# Board_V07B.net
KiCad netlist of a schematic drawn in EAGLE
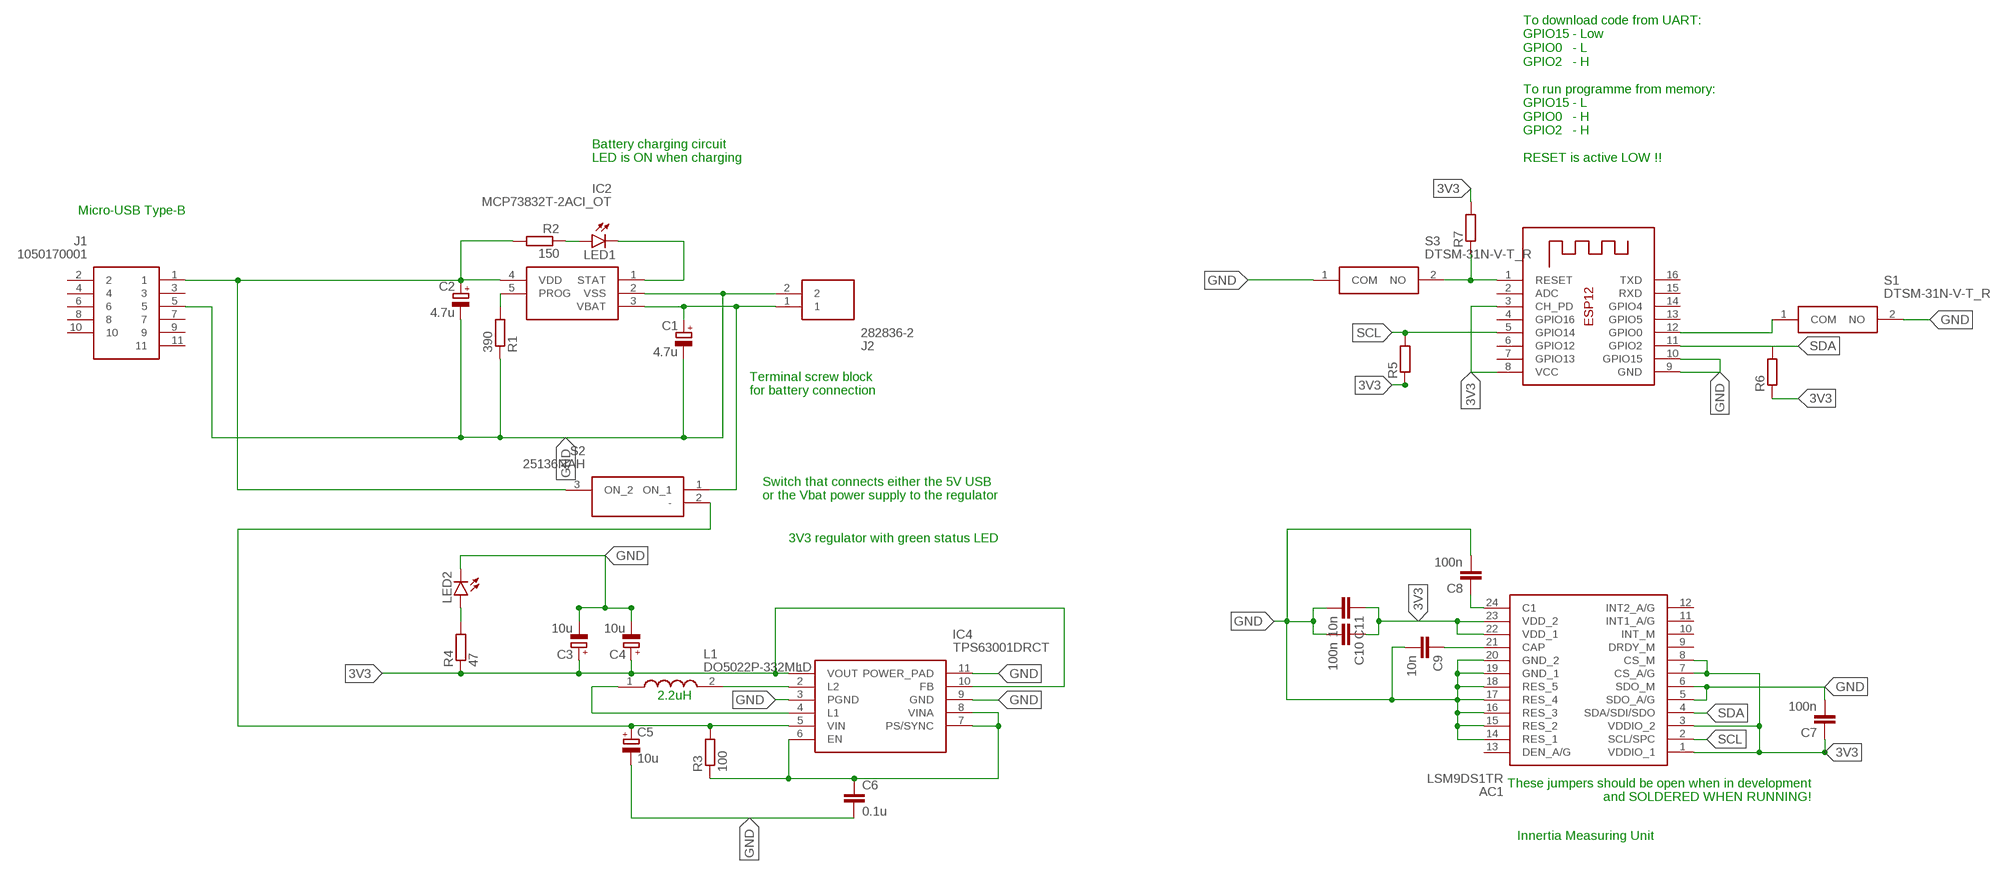
[diagram p0: schematic, sheet 1]

(export (version "E")
  (design (tool "Eeschema 10.0.6"))
  (components
    (comp (ref "AC1")
      (value "LSM9DS1TR")
      (footprint "eagle-import:LGA-24L(3X3.5X1MM)")
      (fields (field (name "MOUSER_PART_NUMBER") "511-LSM9DS1TR") (field (name "RS_PART_NUMBER") "1660908"))
      (libsource (lib "eagle-import") (part "LSM9DS1TR"))
    )
    (comp (ref "C1")
      (value "4.7u")
      (footprint "eagle-import:D_7343-31R")
      (libsource (lib "eagle-import") (part "CPOL-EUD/7343-31R"))
    )
    (comp (ref "C2")
      (value "4.7u")
      (footprint "eagle-import:D_7343-31R")
      (libsource (lib "eagle-import") (part "CPOL-EUD/7343-31R"))
    )
    (comp (ref "C3")
      (value "10u")
      (footprint "eagle-import:D_7343-31R")
      (libsource (lib "eagle-import") (part "CPOL-EUD/7343-31R"))
    )
    (comp (ref "C4")
      (value "10u")
      (footprint "eagle-import:D_7343-31R")
      (libsource (lib "eagle-import") (part "CPOL-EUD/7343-31R"))
    )
    (comp (ref "C5")
      (value "10u")
      (footprint "eagle-import:D_7343-31R")
      (libsource (lib "eagle-import") (part "CPOL-EUD/7343-31R"))
    )
    (comp (ref "C6")
      (value "0.1u")
      (footprint "eagle-import:C0402")
      (libsource (lib "eagle-import") (part "C-EUC0402"))
    )
    (comp (ref "C7")
      (value "100n")
      (footprint "eagle-import:C0805")
      (libsource (lib "eagle-import") (part "C-EUC0805"))
    )
    (comp (ref "C8")
      (value "100n")
      (footprint "eagle-import:C0805")
      (libsource (lib "eagle-import") (part "C-EUC0805"))
    )
    (comp (ref "C9")
      (value "10n")
      (footprint "eagle-import:C0805")
      (libsource (lib "eagle-import") (part "C-EUC0805"))
    )
    (comp (ref "C10")
      (value "100n")
      (footprint "eagle-import:C0805")
      (libsource (lib "eagle-import") (part "C-EUC0805"))
    )
    (comp (ref "C11")
      (value "10n")
      (footprint "eagle-import:C0805")
      (libsource (lib "eagle-import") (part "C-EUC0805"))
    )
    (comp (ref "IC2")
      (value "MCP73832T-2ACI_OT")
      (footprint "eagle-import:SOT95P270X145-5N")
      (fields
        (field (name "MANUFACTURER_PART_NUMBER") "MCP73832T-2ACI/OT")
        (field (name "MOUSER_PART_NUMBER") "579-MCP73832T-2ACIOT")
        (field (name "RS_PART_NUMBER") "9122897")
      )
      (libsource (lib "eagle-import") (part "MCP73832T-2ACI_OT"))
    )
    (comp (ref "IC4")
      (value "TPS63001DRCT")
      (footprint "eagle-import:SON50P300X300X100-11N")
      (fields (field (name "RS_PART_NUMBER") "7968405"))
      (libsource (lib "eagle-import") (part "TPS63001DRCT"))
    )
    (comp (ref "J1")
      (value "1050170001")
      (footprint "eagle-import:MICROUSB-BTYPE")
      (libsource (lib "eagle-import") (part "1050170001"))
    )
    (comp (ref "J2")
      (value "282836-2")
      (footprint "eagle-import:SHDR2W100P0X500_1X2_1000X820X1")
      (fields (field (name "MOUSER_PART_NUMBER") "571-2828362") (field (name "RS_PART_NUMBER") "1354983"))
      (libsource (lib "eagle-import") (part "282836-2"))
    )
    (comp (ref "L1")
      (value "DO5022P-332MLD")
      (footprint "eagle-import:DO5022P-104MLD")
      (fields (field (name "MOUSER_PART_NUMBER") "994-DO5022P-332MLD"))
      (libsource (lib "eagle-import") (part "DO5022P-332MLD"))
    )
    (comp (ref "LED1")
      (value "LED5MM")
      (footprint "eagle-import:LED5MM")
      (libsource (lib "eagle-import") (part "LED5MM"))
    )
    (comp (ref "LED2")
      (value "LED5MM")
      (footprint "eagle-import:LED5MM")
      (libsource (lib "eagle-import") (part "LED5MM"))
    )
    (comp (ref "R1")
      (value "390")
      (footprint "eagle-import:R0805")
      (libsource (lib "eagle-import") (part "R-EU_R0805"))
    )
    (comp (ref "R2")
      (value "150")
      (footprint "eagle-import:R0805")
      (libsource (lib "eagle-import") (part "R-EU_R0805"))
    )
    (comp (ref "R3")
      (value "100")
      (footprint "eagle-import:R0805")
      (libsource (lib "eagle-import") (part "R-EU_R0805"))
    )
    (comp (ref "R4")
      (value "47")
      (footprint "eagle-import:R0805")
      (libsource (lib "eagle-import") (part "R-EU_R0805"))
    )
    (comp (ref "R5")
      (value "R-EU_R0805")
      (footprint "eagle-import:R0805")
      (libsource (lib "eagle-import") (part "R-EU_R0805"))
    )
    (comp (ref "R6")
      (value "R-EU_R0805")
      (footprint "eagle-import:R0805")
      (libsource (lib "eagle-import") (part "R-EU_R0805"))
    )
    (comp (ref "R7")
      (value "R-EU_R0805")
      (footprint "eagle-import:R0805")
      (libsource (lib "eagle-import") (part "R-EU_R0805"))
    )
    (comp (ref "S1")
      (value "DTSM-31N-V-T_R")
      (footprint "eagle-import:DTSM32NVTR")
      (fields
        (field (name "MANUFACTURER_PART_NUMBER") "DTSM-31N-V-T/R")
        (field (name "MOUSER_PART_NUMBER") "113-DTSM31NVTR")
      )
      (libsource (lib "eagle-import") (part "DTSM-31N-V-T_R"))
    )
    (comp (ref "S2")
      (value "25136NAH")
      (footprint "eagle-import:25136NAH")
      (fields (field (name "MOUSER_PART_NUMBER") "642-25136NAH") (field (name "RS_PART_NUMBER") "0339673A"))
      (libsource (lib "eagle-import") (part "25136NAH"))
    )
    (comp (ref "S3")
      (value "DTSM-31N-V-T_R")
      (footprint "eagle-import:DTSM32NVTR")
      (fields
        (field (name "MANUFACTURER_PART_NUMBER") "DTSM-31N-V-T/R")
        (field (name "MOUSER_PART_NUMBER") "113-DTSM31NVTR")
      )
      (libsource (lib "eagle-import") (part "DTSM-31N-V-T_R"))
    )
    (comp (ref "X1")
      (value "ESP-12")
      (footprint "eagle-import:ESP-12")
      (libsource (lib "eagle-import") (part "ESP-12"))
    )
  )
  (nets
    (net (code "1") (name "3V3") (class "Default")
      (node (ref "AC1") (pin "1") (pinfunction "VDDIO_1_1") (pintype "power_in"))
      (node (ref "AC1") (pin "22") (pinfunction "VDD_1_22") (pintype "power_in"))
      (node (ref "AC1") (pin "23") (pinfunction "VDD_2_23") (pintype "power_in"))
      (node (ref "AC1") (pin "3") (pinfunction "VDDIO_2_3") (pintype "power_in"))
      (node (ref "AC1") (pin "7") (pinfunction "CS_A/G_7") (pintype "bidirectional"))
      (node (ref "AC1") (pin "8") (pinfunction "CS_M_8") (pintype "bidirectional"))
      (node (ref "C10") (pin "1") (pinfunction "1_1") (pintype "passive"))
      (node (ref "C11") (pin "1") (pinfunction "1_1") (pintype "passive"))
      (node (ref "C3") (pin "+") (pinfunction "+_+") (pintype "passive"))
      (node (ref "C4") (pin "+") (pinfunction "+_+") (pintype "passive"))
      (node (ref "C7") (pin "1") (pinfunction "1_1") (pintype "passive"))
      (node (ref "IC4") (pin "1") (pinfunction "VOUT_1") (pintype "bidirectional"))
      (node (ref "IC4") (pin "10") (pinfunction "FB_10") (pintype "bidirectional"))
      (node (ref "R4") (pin "1") (pinfunction "1_1") (pintype "passive"))
      (node (ref "R5") (pin "1") (pinfunction "1_1") (pintype "passive"))
      (node (ref "R6") (pin "1") (pinfunction "1_1") (pintype "passive"))
      (node (ref "R7") (pin "2") (pinfunction "2_2") (pintype "passive"))
      (node (ref "X1") (pin "3") (pinfunction "CH_PD_3") (pintype "input"))
      (node (ref "X1") (pin "8") (pinfunction "VCC_8") (pintype "power_in"))
    )
    (net (code "2") (name "GND") (class "Default")
      (node (ref "AC1") (pin "14") (pinfunction "RES_1_14") (pintype "power_in"))
      (node (ref "AC1") (pin "15") (pinfunction "RES_2_15") (pintype "power_in"))
      (node (ref "AC1") (pin "16") (pinfunction "RES_3_16") (pintype "power_in"))
      (node (ref "AC1") (pin "17") (pinfunction "RES_4_17") (pintype "power_in"))
      (node (ref "AC1") (pin "18") (pinfunction "RES_5_18") (pintype "power_in"))
      (node (ref "AC1") (pin "19") (pinfunction "GND_1_19") (pintype "power_in"))
      (node (ref "AC1") (pin "20") (pinfunction "GND_2_20") (pintype "power_in"))
      (node (ref "AC1") (pin "5") (pinfunction "SDO_A/G_5") (pintype "output"))
      (node (ref "AC1") (pin "6") (pinfunction "SDO_M_6") (pintype "output"))
      (node (ref "C1") (pin "-") (pinfunction "-_-") (pintype "passive"))
      (node (ref "C10") (pin "2") (pinfunction "2_2") (pintype "passive"))
      (node (ref "C11") (pin "2") (pinfunction "2_2") (pintype "passive"))
      (node (ref "C2") (pin "-") (pinfunction "-_-") (pintype "passive"))
      (node (ref "C3") (pin "-") (pinfunction "-_-") (pintype "passive"))
      (node (ref "C4") (pin "-") (pinfunction "-_-") (pintype "passive"))
      (node (ref "C5") (pin "-") (pinfunction "-_-") (pintype "passive"))
      (node (ref "C6") (pin "2") (pinfunction "2_2") (pintype "passive"))
      (node (ref "C7") (pin "2") (pinfunction "2_2") (pintype "passive"))
      (node (ref "C8") (pin "2") (pinfunction "2_2") (pintype "passive"))
      (node (ref "C9") (pin "2") (pinfunction "2_2") (pintype "passive"))
      (node (ref "IC2") (pin "2") (pinfunction "VSS_2") (pintype "power_in"))
      (node (ref "IC4") (pin "11") (pinfunction "POWER_PAD_11") (pintype "bidirectional"))
      (node (ref "IC4") (pin "3") (pinfunction "PGND_3") (pintype "bidirectional"))
      (node (ref "IC4") (pin "9") (pinfunction "GND_9") (pintype "bidirectional"))
      (node (ref "J1") (pin "5") (pinfunction "5_5") (pintype "bidirectional"))
      (node (ref "J2") (pin "2") (pinfunction "2_2") (pintype "bidirectional"))
      (node (ref "LED2") (pin "K") (pinfunction "C_K") (pintype "passive"))
      (node (ref "R1") (pin "1") (pinfunction "1_1") (pintype "passive"))
      (node (ref "S1") (pin "2") (pinfunction "NO_2") (pintype "bidirectional"))
      (node (ref "S3") (pin "1") (pinfunction "COM_1") (pintype "bidirectional"))
      (node (ref "X1") (pin "10") (pinfunction "GPIO15_10") (pintype "bidirectional"))
      (node (ref "X1") (pin "9") (pinfunction "GND_9") (pintype "power_in"))
    )
    (net (code "3") (name "Net-(AC1-C1)") (class "Default")
      (node (ref "AC1") (pin "24") (pinfunction "C1_24") (pintype "bidirectional"))
      (node (ref "C8") (pin "1") (pinfunction "1_1") (pintype "passive"))
    )
    (net (code "4") (name "Net-(AC1-CAP)") (class "Default")
      (node (ref "AC1") (pin "21") (pinfunction "CAP_21") (pintype "power_in"))
      (node (ref "C9") (pin "1") (pinfunction "1_1") (pintype "passive"))
    )
    (net (code "5") (name "Net-(IC2-PROG)") (class "Default")
      (node (ref "IC2") (pin "5") (pinfunction "PROG_5") (pintype "bidirectional"))
      (node (ref "R1") (pin "2") (pinfunction "2_2") (pintype "passive"))
    )
    (net (code "6") (name "Net-(IC2-STAT)") (class "Default")
      (node (ref "IC2") (pin "1") (pinfunction "STAT_1") (pintype "bidirectional"))
      (node (ref "LED1") (pin "K") (pinfunction "C_K") (pintype "passive"))
    )
    (net (code "7") (name "Net-(IC2-VBAT)") (class "Default")
      (node (ref "C1") (pin "+") (pinfunction "+_+") (pintype "passive"))
      (node (ref "IC2") (pin "3") (pinfunction "VBAT_3") (pintype "bidirectional"))
      (node (ref "J2") (pin "1") (pinfunction "1_1") (pintype "bidirectional"))
      (node (ref "S2") (pin "1") (pinfunction "ON_1_1") (pintype "bidirectional"))
    )
    (net (code "8") (name "Net-(IC2-VDD)") (class "Default")
      (node (ref "C2") (pin "+") (pinfunction "+_+") (pintype "passive"))
      (node (ref "IC2") (pin "4") (pinfunction "VDD_4") (pintype "power_in"))
      (node (ref "J1") (pin "1") (pinfunction "1_1") (pintype "bidirectional"))
      (node (ref "R2") (pin "2") (pinfunction "2_2") (pintype "passive"))
      (node (ref "S2") (pin "3") (pinfunction "ON_2_3") (pintype "bidirectional"))
    )
    (net (code "9") (name "Net-(IC4-EN)") (class "Default")
      (node (ref "C6") (pin "1") (pinfunction "1_1") (pintype "passive"))
      (node (ref "IC4") (pin "6") (pinfunction "EN_6") (pintype "bidirectional"))
      (node (ref "IC4") (pin "7") (pinfunction "PS/SYNC_7") (pintype "bidirectional"))
      (node (ref "IC4") (pin "8") (pinfunction "VINA_8") (pintype "bidirectional"))
      (node (ref "R3") (pin "1") (pinfunction "1_1") (pintype "passive"))
    )
    (net (code "10") (name "Net-(IC4-L1)") (class "Default")
      (node (ref "IC4") (pin "4") (pinfunction "L1_4") (pintype "bidirectional"))
      (node (ref "L1") (pin "1") (pinfunction "1_1") (pintype "bidirectional"))
    )
    (net (code "11") (name "Net-(IC4-L2)") (class "Default")
      (node (ref "IC4") (pin "2") (pinfunction "L2_2") (pintype "bidirectional"))
      (node (ref "L1") (pin "2") (pinfunction "2_2") (pintype "bidirectional"))
    )
    (net (code "12") (name "Net-(IC4-VIN)") (class "Default")
      (node (ref "C5") (pin "+") (pinfunction "+_+") (pintype "passive"))
      (node (ref "IC4") (pin "5") (pinfunction "VIN_5") (pintype "bidirectional"))
      (node (ref "R3") (pin "2") (pinfunction "2_2") (pintype "passive"))
      (node (ref "S2") (pin "2") (pinfunction "-_2") (pintype "bidirectional"))
    )
    (net (code "13") (name "Net-(LED1-PadA)") (class "Default")
      (node (ref "LED1") (pin "A") (pinfunction "A_A") (pintype "passive"))
      (node (ref "R2") (pin "1") (pinfunction "1_1") (pintype "passive"))
    )
    (net (code "14") (name "Net-(LED2-PadA)") (class "Default")
      (node (ref "LED2") (pin "A") (pinfunction "A_A") (pintype "passive"))
      (node (ref "R4") (pin "2") (pinfunction "2_2") (pintype "passive"))
    )
    (net (code "15") (name "Net-(S1-COM)") (class "Default")
      (node (ref "S1") (pin "1") (pinfunction "COM_1") (pintype "bidirectional"))
      (node (ref "X1") (pin "12") (pinfunction "GPIO0_12") (pintype "bidirectional"))
    )
    (net (code "16") (name "Net-(S3-NO)") (class "Default")
      (node (ref "R7") (pin "1") (pinfunction "1_1") (pintype "passive"))
      (node (ref "S3") (pin "2") (pinfunction "NO_2") (pintype "bidirectional"))
      (node (ref "X1") (pin "1") (pinfunction "RESET_1") (pintype "input"))
    )
    (net (code "17") (name "SCL") (class "Default")
      (node (ref "AC1") (pin "2") (pinfunction "SCL/SPC_2") (pintype "output"))
      (node (ref "R5") (pin "2") (pinfunction "2_2") (pintype "passive"))
      (node (ref "X1") (pin "5") (pinfunction "GPIO14_5") (pintype "bidirectional"))
    )
    (net (code "18") (name "SDA") (class "Default")
      (node (ref "AC1") (pin "4") (pinfunction "SDA/SDI/SDO_4") (pintype "bidirectional"))
      (node (ref "R6") (pin "2") (pinfunction "2_2") (pintype "passive"))
      (node (ref "X1") (pin "11") (pinfunction "GPIO2_11") (pintype "bidirectional"))
    )
    (net (code "19") (name "unconnected-(AC1-DEN_A{slash}G-Pad13)") (class "Default")
      (node (ref "AC1") (pin "13") (pinfunction "DEN_A/G_13") (pintype "bidirectional"))
    )
    (net (code "20") (name "unconnected-(AC1-DRDY_M-Pad9)") (class "Default")
      (node (ref "AC1") (pin "9") (pinfunction "DRDY_M_9") (pintype "bidirectional"))
    )
    (net (code "21") (name "unconnected-(AC1-INT1_A{slash}G-Pad11)") (class "Default")
      (node (ref "AC1") (pin "11") (pinfunction "INT1_A/G_11") (pintype "bidirectional"))
    )
    (net (code "22") (name "unconnected-(AC1-INT2_A{slash}G-Pad12)") (class "Default")
      (node (ref "AC1") (pin "12") (pinfunction "INT2_A/G_12") (pintype "bidirectional"))
    )
    (net (code "23") (name "unconnected-(AC1-INT_M-Pad10)") (class "Default")
      (node (ref "AC1") (pin "10") (pinfunction "INT_M_10") (pintype "bidirectional"))
    )
    (net (code "24") (name "unconnected-(J1-Pad2)") (class "Default")
      (node (ref "J1") (pin "2") (pinfunction "2_2") (pintype "bidirectional"))
    )
    (net (code "25") (name "unconnected-(J1-Pad3)") (class "Default")
      (node (ref "J1") (pin "3") (pinfunction "3_3") (pintype "bidirectional"))
    )
    (net (code "26") (name "unconnected-(J1-Pad4)") (class "Default")
      (node (ref "J1") (pin "4") (pinfunction "4_4") (pintype "bidirectional"))
    )
    (net (code "27") (name "unconnected-(J1-Pad6)") (class "Default")
      (node (ref "J1") (pin "6") (pinfunction "6_6") (pintype "bidirectional"))
    )
    (net (code "28") (name "unconnected-(J1-Pad7)") (class "Default")
      (node (ref "J1") (pin "7") (pinfunction "7_7") (pintype "bidirectional"))
    )
    (net (code "29") (name "unconnected-(J1-Pad8)") (class "Default")
      (node (ref "J1") (pin "8") (pinfunction "8_8") (pintype "bidirectional"))
    )
    (net (code "30") (name "unconnected-(J1-Pad9)") (class "Default")
      (node (ref "J1") (pin "9") (pinfunction "9_9") (pintype "bidirectional"))
    )
    (net (code "31") (name "unconnected-(J1-Pad10)") (class "Default")
      (node (ref "J1") (pin "10") (pinfunction "10_10") (pintype "bidirectional"))
    )
    (net (code "32") (name "unconnected-(J1-Pad11)") (class "Default")
      (node (ref "J1") (pin "11") (pinfunction "11_11") (pintype "bidirectional"))
    )
    (net (code "33") (name "unconnected-(X1-ADC-Pad2)") (class "Default")
      (node (ref "X1") (pin "2") (pinfunction "ADC_2") (pintype "passive"))
    )
    (net (code "34") (name "unconnected-(X1-GPIO4-Pad14)") (class "Default")
      (node (ref "X1") (pin "14") (pinfunction "GPIO4_14") (pintype "bidirectional"))
    )
    (net (code "35") (name "unconnected-(X1-GPIO5-Pad13)") (class "Default")
      (node (ref "X1") (pin "13") (pinfunction "GPIO5_13") (pintype "bidirectional"))
    )
    (net (code "36") (name "unconnected-(X1-GPIO12-Pad6)") (class "Default")
      (node (ref "X1") (pin "6") (pinfunction "GPIO12_6") (pintype "bidirectional"))
    )
    (net (code "37") (name "unconnected-(X1-GPIO13-Pad7)") (class "Default")
      (node (ref "X1") (pin "7") (pinfunction "GPIO13_7") (pintype "bidirectional"))
    )
    (net (code "38") (name "unconnected-(X1-GPIO16-Pad4)") (class "Default")
      (node (ref "X1") (pin "4") (pinfunction "GPIO16_4") (pintype "bidirectional"))
    )
    (net (code "39") (name "unconnected-(X1-RXD-Pad15)") (class "Default")
      (node (ref "X1") (pin "15") (pinfunction "RXD_15") (pintype "input"))
    )
    (net (code "40") (name "unconnected-(X1-TXD-Pad16)") (class "Default")
      (node (ref "X1") (pin "16") (pinfunction "TXD_16") (pintype "output"))
    )
  )
)
